# 03_Mini_USB_Circuit.net
KiCad netlist of a schematic drawn in Altium Designer
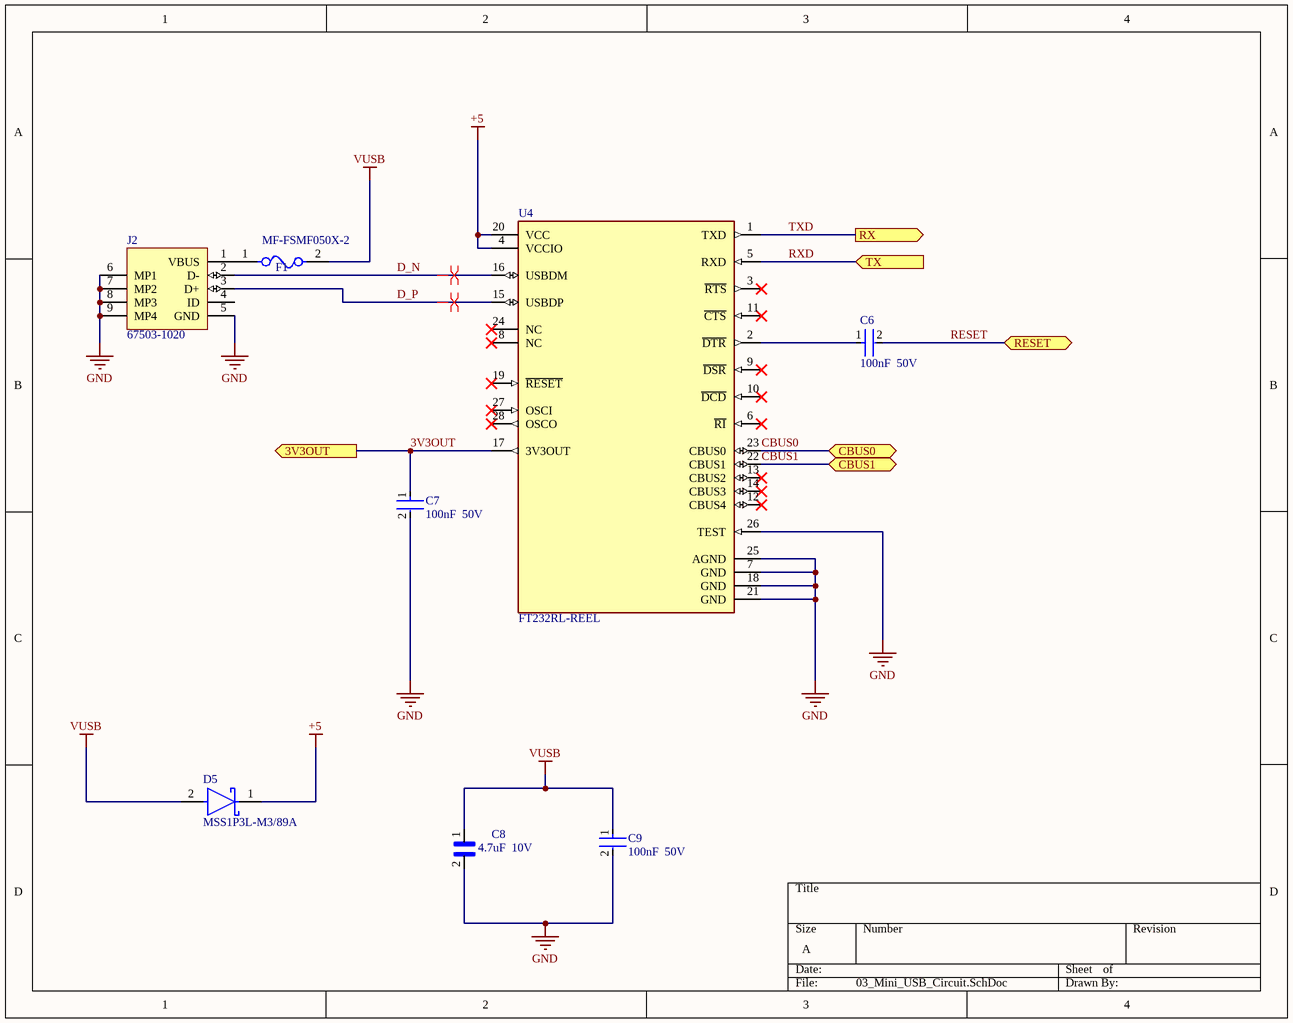
[diagram p0: 03_Mini_USB_Circuit.SchDoc]

(export (version "E")
  (design (tool "Eeschema 10.0.6"))
  (components
    (comp (ref "C6")
      (value "100nF  50V")
      (footprint "FP-0805-L_2_01_0_2-W_1_25-IPC_C")
      (description "General Purpose Ceramic Capacitor, 0805, 100nF, 10%, X7R, 0.15, 50V")
      (fields (field (name "TOLERANCE") "10%") (field (name "VOLTAGE") "50V"))
      (libsource (lib "Altium Content Vault") (part "02cd4be3c70576c341d710602a673aa"))
    )
    (comp (ref "C7")
      (value "100nF  50V")
      (footprint "FP-0805-L_2_01_0_2-W_1_25-IPC_C")
      (description "General Purpose Ceramic Capacitor, 0805, 100nF, 10%, X7R, 0.15, 50V")
      (fields (field (name "TOLERANCE") "10%") (field (name "VOLTAGE") "50V"))
      (libsource (lib "Altium Content Vault") (part "02cd4be3c70576c341d710602a673aa"))
    )
    (comp (ref "C8")
      (value "4.7uF  10V")
      (footprint "CAPC1608X90")
      (libsource (lib "CC0603ZRY5V5BB475") (part "CC0603ZRY5V5BB475"))
    )
    (comp (ref "C9")
      (value "100nF  50V")
      (footprint "FP-0805-L_2_01_0_2-W_1_25-IPC_C")
      (description "General Purpose Ceramic Capacitor, 0805, 100nF, 10%, X7R, 0.15, 50V")
      (fields (field (name "TOLERANCE") "10%") (field (name "VOLTAGE") "50V"))
      (libsource (lib "Altium Content Vault") (part "02cd4be3c70576c341d710602a673aa"))
    )
    (comp (ref "D5")
      (value "MSS1P3L-M3/89A")
      (footprint "FP-96591-MFG")
      (description "DIODE SCHOTTKY 30V 1A MICROSMP")
      (fields
        (field (name "OCTOPART") "https://octopart.com/mss1p3l-m3%2F89a-vishay-42670898")
        (field (name "MANUFACTURER") "Vishay")
      )
      (libsource (lib "Altium Content Vault") (part "1d6ec82d83fb6aee721767c19dac4b9"))
    )
    (comp (ref "F1")
      (value "MF-FSMF050X-2")
      (footprint "FP-MF-FSMF-MFG")
      (description "PTC RESET FUSE 6V 500MA 0603")
      (fields
        (field (name "MANUFACTURER") "Bourns Inc.")
        (field (name "OCTOPART") "https://octopart.com/mf-fsmf050x-2-bourns-10470804")
      )
      (libsource (lib "Altium Content Vault") (part "5bcf9b9f640e542cf0359d10258e979"))
    )
    (comp (ref "J2")
      (value "67503-1020")
      (footprint "MOLX-67503-1020_V")
      (description "USB, MINI, SMD, RA KME04-USBMU03A01")
      (fields (field (name "MANUFACTURER") "Molex"))
      (libsource (lib "Altium Content Vault") (part "MOLX-67503-1020"))
    )
    (comp (ref "U4")
      (value "FT232RL-REEL")
      (footprint "FP-SSOP-28-MFG")
      (description "IC USB FS SERIAL UART 28-SSOP")
      (fields (field (name "VOLTAGE") "5V"))
      (libsource (lib "Altium Content Vault") (part "fa727c664f4d88ca0f1b580aa0dd901"))
    )
  )
  (nets
    (net (code "1") (name "+5") (class "Default")
      (node (ref "D5") (pin "1") (pinfunction "C_1") (pintype "passive"))
      (node (ref "U4") (pin "20") (pinfunction "VCC_20") (pintype "power_in"))
      (node (ref "U4") (pin "4") (pinfunction "VCCIO_4") (pintype "power_in"))
    )
    (net (code "2") (name "/3V3OUT") (class "Default")
      (node (ref "C7") (pin "1") (pinfunction "1_1") (pintype "passive"))
      (node (ref "U4") (pin "17") (pinfunction "3V3OUT_17") (pintype "output"))
    )
    (net (code "3") (name "/CBUS0") (class "Default")
      (node (ref "U4") (pin "23") (pinfunction "CBUS0_23") (pintype "bidirectional"))
    )
    (net (code "4") (name "/CBUS1") (class "Default")
      (node (ref "U4") (pin "22") (pinfunction "CBUS1_22") (pintype "bidirectional"))
    )
    (net (code "5") (name "/D_N") (class "Default")
      (node (ref "J2") (pin "2") (pinfunction "D-_2") (pintype "bidirectional"))
      (node (ref "U4") (pin "16") (pinfunction "USBDM_16") (pintype "bidirectional"))
    )
    (net (code "6") (name "/D_P") (class "Default")
      (node (ref "J2") (pin "3") (pinfunction "D+_3") (pintype "bidirectional"))
      (node (ref "U4") (pin "15") (pinfunction "USBDP_15") (pintype "bidirectional"))
    )
    (net (code "7") (name "/RESET") (class "Default")
      (node (ref "C6") (pin "2") (pinfunction "2_2") (pintype "passive"))
    )
    (net (code "8") (name "/RXD") (class "Default")
      (node (ref "U4") (pin "5") (pinfunction "RXD_5") (pintype "input"))
    )
    (net (code "9") (name "/TXD") (class "Default")
      (node (ref "U4") (pin "1") (pinfunction "TXD_1") (pintype "output"))
    )
    (net (code "10") (name "GND") (class "Default")
      (node (ref "C7") (pin "2") (pinfunction "2_2") (pintype "passive"))
      (node (ref "C8") (pin "2") (pinfunction "2_2") (pintype "passive"))
      (node (ref "C9") (pin "2") (pinfunction "2_2") (pintype "passive"))
      (node (ref "J2") (pin "5") (pinfunction "GND_5") (pintype "power_in"))
      (node (ref "J2") (pin "6") (pinfunction "MP1_6") (pintype "passive"))
      (node (ref "J2") (pin "7") (pinfunction "MP2_7") (pintype "passive"))
      (node (ref "J2") (pin "8") (pinfunction "MP3_8") (pintype "passive"))
      (node (ref "J2") (pin "9") (pinfunction "MP4_9") (pintype "passive"))
      (node (ref "U4") (pin "18") (pinfunction "GND_18") (pintype "power_in"))
      (node (ref "U4") (pin "21") (pinfunction "GND_21") (pintype "power_in"))
      (node (ref "U4") (pin "25") (pinfunction "AGND_25") (pintype "power_in"))
      (node (ref "U4") (pin "26") (pinfunction "TEST_26") (pintype "input"))
      (node (ref "U4") (pin "7") (pinfunction "GND_7") (pintype "power_in"))
    )
    (net (code "11") (name "Net-(J2-VBUS)") (class "Default")
      (node (ref "F1") (pin "1") (pinfunction "1_1") (pintype "passive"))
      (node (ref "J2") (pin "1") (pinfunction "VBUS_1") (pintype "power_in"))
    )
    (net (code "12") (name "Net-(U4-~{DTR})") (class "Default")
      (node (ref "C6") (pin "1") (pinfunction "1_1") (pintype "passive"))
      (node (ref "U4") (pin "2") (pinfunction "~{DTR}_2") (pintype "output"))
    )
    (net (code "13") (name "VUSB") (class "Default")
      (node (ref "C8") (pin "1") (pinfunction "1_1") (pintype "passive"))
      (node (ref "C9") (pin "1") (pinfunction "1_1") (pintype "passive"))
      (node (ref "D5") (pin "2") (pinfunction "A_2") (pintype "passive"))
      (node (ref "F1") (pin "2") (pinfunction "2_2") (pintype "passive"))
    )
    (net (code "14") (name "unconnected-(J2-ID-Pad4)") (class "Default")
      (node (ref "J2") (pin "4") (pinfunction "ID_4") (pintype "passive"))
    )
    (net (code "15") (name "unconnected-(U4-CBUS2-Pad13)") (class "Default")
      (node (ref "U4") (pin "13") (pinfunction "CBUS2_13") (pintype "bidirectional+no_connect"))
    )
    (net (code "16") (name "unconnected-(U4-CBUS3-Pad14)") (class "Default")
      (node (ref "U4") (pin "14") (pinfunction "CBUS3_14") (pintype "bidirectional+no_connect"))
    )
    (net (code "17") (name "unconnected-(U4-CBUS4-Pad12)") (class "Default")
      (node (ref "U4") (pin "12") (pinfunction "CBUS4_12") (pintype "bidirectional+no_connect"))
    )
    (net (code "18") (name "unconnected-(U4-NC-Pad8)") (class "Default")
      (node (ref "U4") (pin "8") (pinfunction "NC_8") (pintype "passive+no_connect"))
    )
    (net (code "19") (name "unconnected-(U4-NC-Pad24)") (class "Default")
      (node (ref "U4") (pin "24") (pinfunction "NC_24") (pintype "passive+no_connect"))
    )
    (net (code "20") (name "unconnected-(U4-OSCI-Pad27)") (class "Default")
      (node (ref "U4") (pin "27") (pinfunction "OSCI_27") (pintype "input+no_connect"))
    )
    (net (code "21") (name "unconnected-(U4-OSCO-Pad28)") (class "Default")
      (node (ref "U4") (pin "28") (pinfunction "OSCO_28") (pintype "output+no_connect"))
    )
    (net (code "22") (name "unconnected-(U4-~{CTS}-Pad11)") (class "Default")
      (node (ref "U4") (pin "11") (pinfunction "~{CTS}_11") (pintype "input+no_connect"))
    )
    (net (code "23") (name "unconnected-(U4-~{DCD}-Pad10)") (class "Default")
      (node (ref "U4") (pin "10") (pinfunction "~{DCD}_10") (pintype "input+no_connect"))
    )
    (net (code "24") (name "unconnected-(U4-~{DSR}-Pad9)") (class "Default")
      (node (ref "U4") (pin "9") (pinfunction "~{DSR}_9") (pintype "input+no_connect"))
    )
    (net (code "25") (name "unconnected-(U4-~{RESET}-Pad19)") (class "Default")
      (node (ref "U4") (pin "19") (pinfunction "~{RESET}_19") (pintype "input+no_connect"))
    )
    (net (code "26") (name "unconnected-(U4-~{RI}-Pad6)") (class "Default")
      (node (ref "U4") (pin "6") (pinfunction "~{RI}_6") (pintype "input+no_connect"))
    )
    (net (code "27") (name "unconnected-(U4-~{RTS}-Pad3)") (class "Default")
      (node (ref "U4") (pin "3") (pinfunction "~{RTS}_3") (pintype "output+no_connect"))
    )
  )
)
